# R3S601.net
KiCad netlist of a schematic drawn in Altium Designer
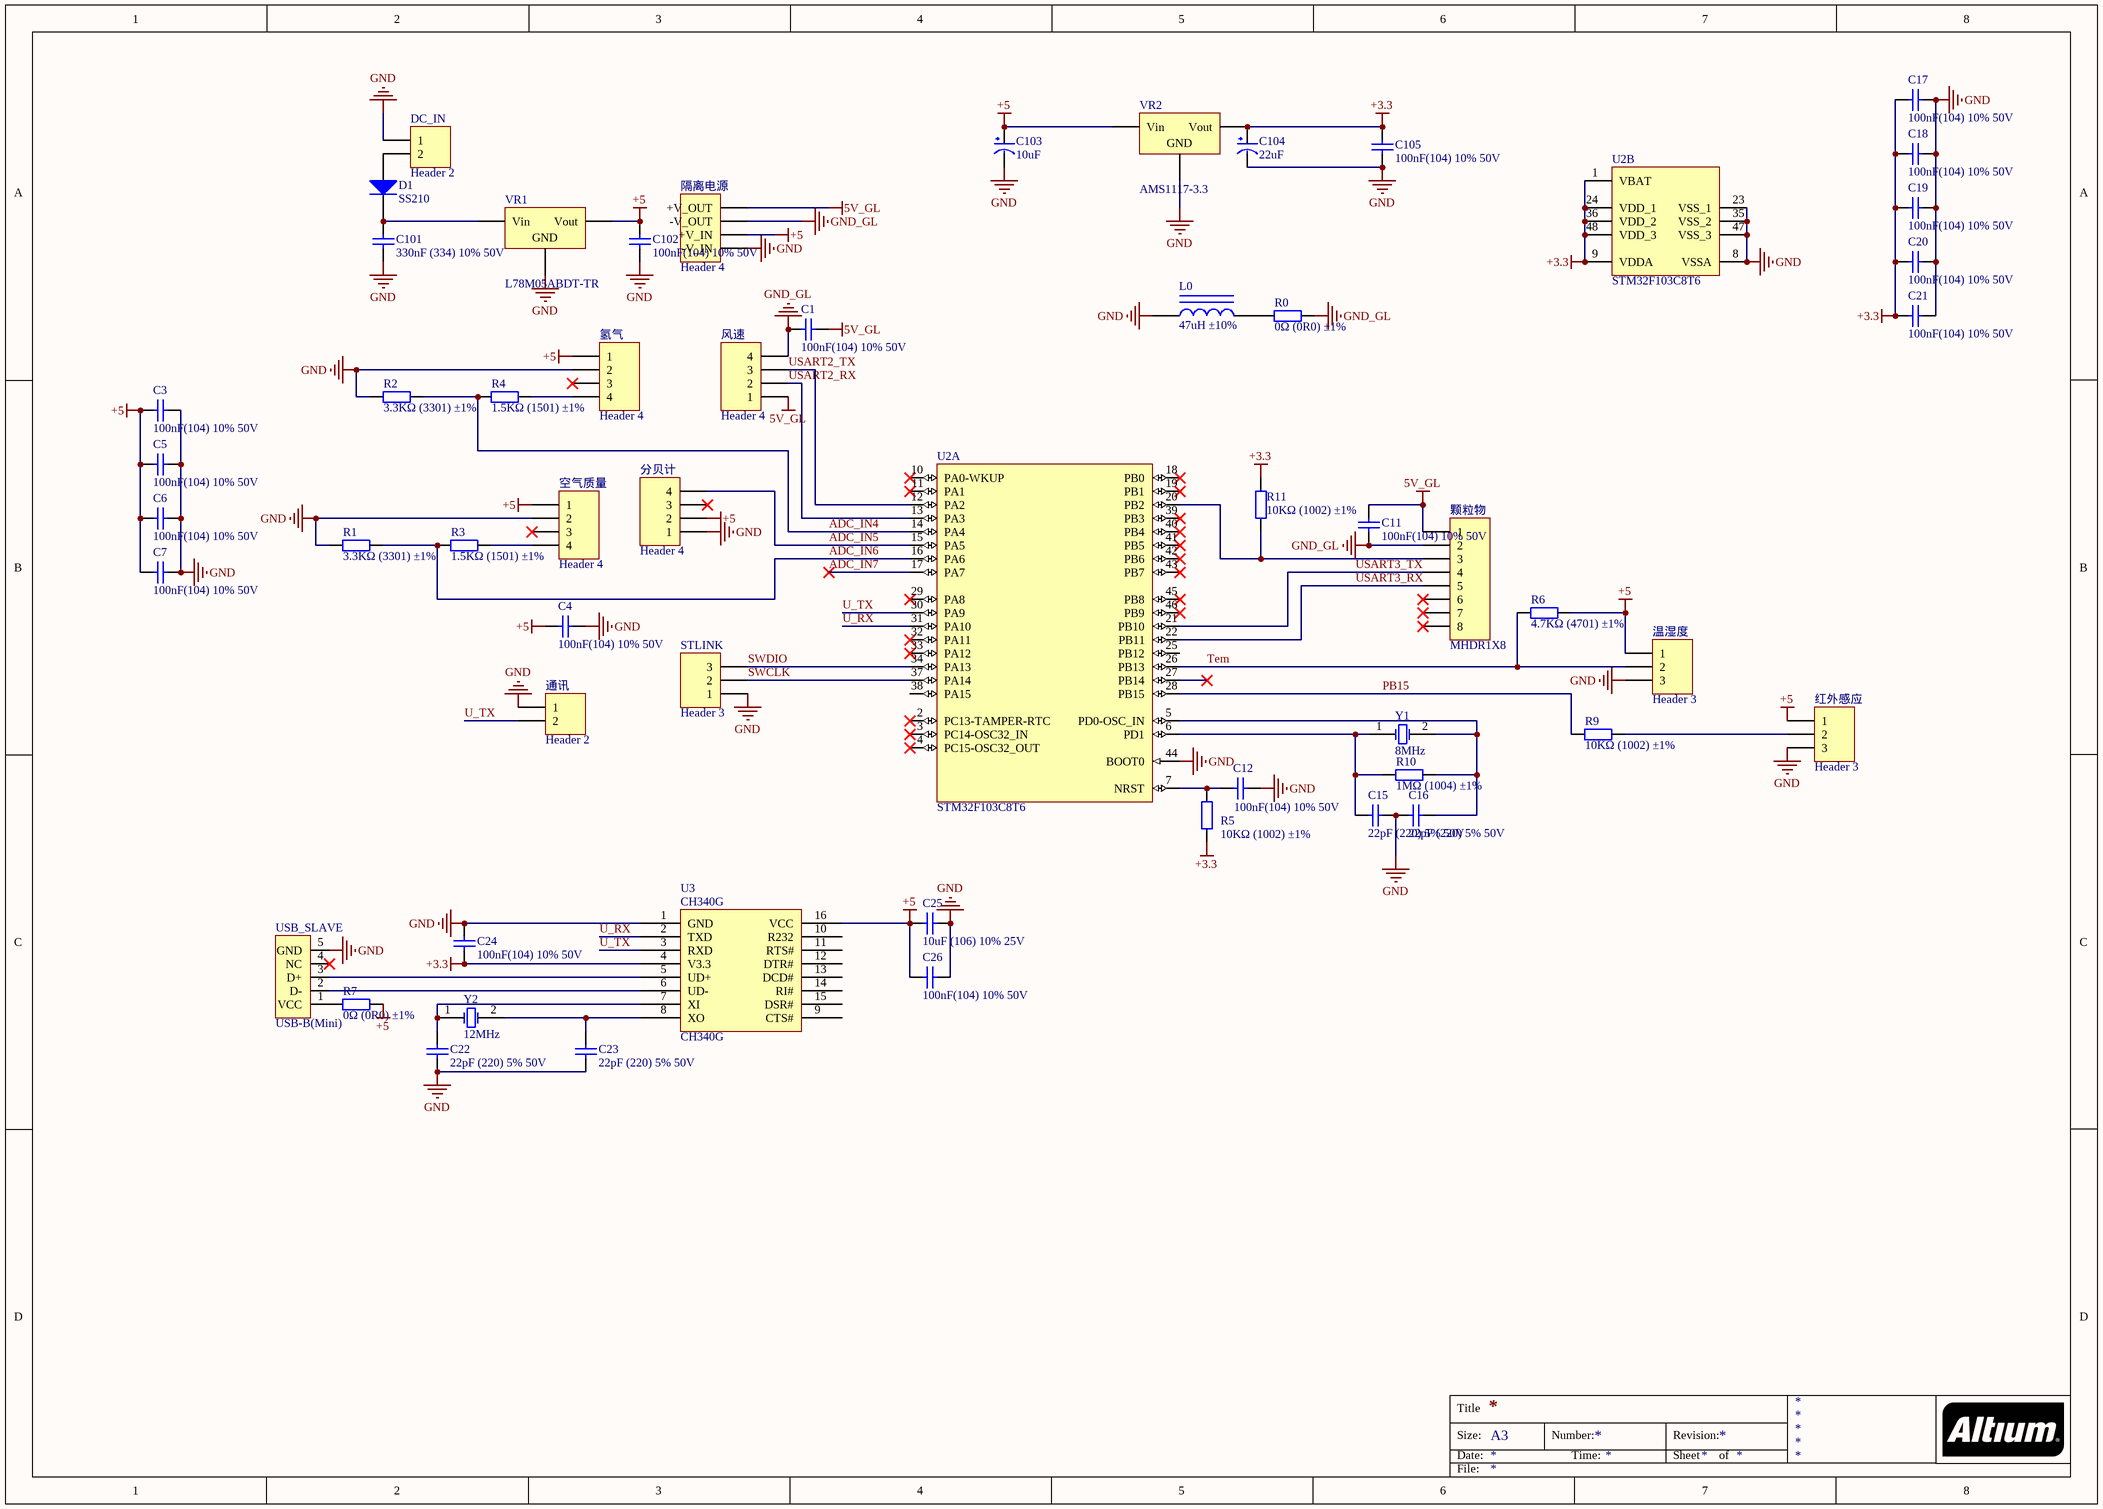
[diagram p0: R3S601.SchDoc]

(export (version "E")
  (design (tool "Eeschema 10.0.6"))
  (components
    (comp (ref "C1")
      (value "100nF(104) 10% 50V")
      (footprint "LC-0805_C")
      (description "贴片电容")
      (libsource (lib "Miscellaneous Devices LC") (part "0805 100nF(104) 10% 50V"))
    )
    (comp (ref "C3")
      (value "100nF(104) 10% 50V")
      (footprint "LC-0805_C")
      (description "贴片电容")
      (libsource (lib "Miscellaneous Devices LC") (part "0805 100nF(104) 10% 50V"))
    )
    (comp (ref "C4")
      (value "100nF(104) 10% 50V")
      (footprint "LC-0805_C")
      (description "贴片电容")
      (libsource (lib "Miscellaneous Devices LC") (part "0805 100nF(104) 10% 50V"))
    )
    (comp (ref "C5")
      (value "100nF(104) 10% 50V")
      (footprint "LC-0805_C")
      (description "贴片电容")
      (libsource (lib "Miscellaneous Devices LC") (part "0805 100nF(104) 10% 50V"))
    )
    (comp (ref "C6")
      (value "100nF(104) 10% 50V")
      (footprint "LC-0805_C")
      (description "贴片电容")
      (libsource (lib "Miscellaneous Devices LC") (part "0805 100nF(104) 10% 50V"))
    )
    (comp (ref "C7")
      (value "100nF(104) 10% 50V")
      (footprint "LC-0805_C")
      (description "贴片电容")
      (libsource (lib "Miscellaneous Devices LC") (part "0805 100nF(104) 10% 50V"))
    )
    (comp (ref "C11")
      (value "100nF(104) 10% 50V")
      (footprint "LC-0805_C")
      (description "贴片电容")
      (libsource (lib "Miscellaneous Devices LC") (part "0805 100nF(104) 10% 50V"))
    )
    (comp (ref "C12")
      (value "100nF(104) 10% 50V")
      (footprint "LC-0805_C")
      (description "贴片电容")
      (libsource (lib "Miscellaneous Devices LC") (part "0805 100nF(104) 10% 50V"))
    )
    (comp (ref "C15")
      (value "22pF (220) 5% 50V")
      (footprint "LC-0805_C")
      (description "贴片电容")
      (libsource (lib "Miscellaneous Devices LC") (part "0805 22pF (220) 5% 50V"))
    )
    (comp (ref "C16")
      (value "22pF (220) 5% 50V")
      (footprint "LC-0805_C")
      (description "贴片电容")
      (libsource (lib "Miscellaneous Devices LC") (part "0805 22pF (220) 5% 50V"))
    )
    (comp (ref "C17")
      (value "100nF(104) 10% 50V")
      (footprint "LC-0805_C")
      (description "贴片电容")
      (libsource (lib "Miscellaneous Devices LC") (part "0805 100nF(104) 10% 50V"))
    )
    (comp (ref "C18")
      (value "100nF(104) 10% 50V")
      (footprint "LC-0805_C")
      (description "贴片电容")
      (libsource (lib "Miscellaneous Devices LC") (part "0805 100nF(104) 10% 50V"))
    )
    (comp (ref "C19")
      (value "100nF(104) 10% 50V")
      (footprint "LC-0805_C")
      (description "贴片电容")
      (libsource (lib "Miscellaneous Devices LC") (part "0805 100nF(104) 10% 50V"))
    )
    (comp (ref "C20")
      (value "100nF(104) 10% 50V")
      (footprint "LC-0805_C")
      (description "贴片电容")
      (libsource (lib "Miscellaneous Devices LC") (part "0805 100nF(104) 10% 50V"))
    )
    (comp (ref "C21")
      (value "100nF(104) 10% 50V")
      (footprint "LC-0805_C")
      (description "贴片电容")
      (libsource (lib "Miscellaneous Devices LC") (part "0805 100nF(104) 10% 50V"))
    )
    (comp (ref "C22")
      (value "22pF (220) 5% 50V")
      (footprint "LC-0805_C")
      (description "贴片电容")
      (libsource (lib "Miscellaneous Devices LC") (part "0805 22pF (220) 5% 50V"))
    )
    (comp (ref "C23")
      (value "22pF (220) 5% 50V")
      (footprint "LC-0805_C")
      (description "贴片电容")
      (libsource (lib "Miscellaneous Devices LC") (part "0805 22pF (220) 5% 50V"))
    )
    (comp (ref "C24")
      (value "100nF(104) 10% 50V")
      (footprint "LC-0805_C")
      (description "贴片电容")
      (libsource (lib "Miscellaneous Devices LC") (part "0805 100nF(104) 10% 50V"))
    )
    (comp (ref "C25")
      (value "10uF (106) 10% 25V")
      (footprint "LC-0805_C")
      (description "贴片电容")
      (libsource (lib "Miscellaneous Devices LC") (part "0805 10uF (106) 10% 25V"))
    )
    (comp (ref "C26")
      (value "100nF(104) 10% 50V")
      (footprint "LC-0805_C")
      (description "贴片电容")
      (libsource (lib "Miscellaneous Devices LC") (part "0805 100nF(104) 10% 50V"))
    )
    (comp (ref "C101")
      (value "330nF (334) 10% 50V")
      (footprint "LC-0805_C")
      (description "贴片电容")
      (libsource (lib "Miscellaneous Devices LC") (part "0805 330nF (334) 10% 50V"))
    )
    (comp (ref "C102")
      (value "100nF(104) 10% 50V")
      (footprint "LC-0805_C")
      (description "贴片电容")
      (libsource (lib "Miscellaneous Devices LC") (part "0805 100nF(104) 10% 50V"))
    )
    (comp (ref "C103")
      (value "10uF")
      (footprint "CC6.56.5")
      (libsource (lib "Explorer STM32F407封装库") (part "CAP"))
    )
    (comp (ref "C104")
      (value "22uF")
      (footprint "CC6.56.5")
      (libsource (lib "Explorer STM32F407封装库") (part "CAP"))
    )
    (comp (ref "C105")
      (value "100nF(104) 10% 50V")
      (footprint "LC-0805_C")
      (description "贴片电容")
      (libsource (lib "Miscellaneous Devices LC") (part "0805 100nF(104) 10% 50V"))
    )
    (comp (ref "D1")
      (value "SS210")
      (footprint "LC-SMA(DO-214AC)_S1")
      (description "二极管")
      (libsource (lib "Miscellaneous Devices LC") (part "SMA(DO-214AC) SS210"))
    )
    (comp (ref "DC_IN")
      (value "Header 2")
      (footprint "HDR1X2")
      (description "Header, 2-Pin")
      (fields (field (name "PUBLISHER") "Altium Limited"))
      (libsource (lib "Miscellaneous Connectors") (part "Header 2"))
    )
    (comp (ref "L0")
      (value "47uH ±10%")
      (footprint "LC-0805_L")
      (description "贴片电感")
      (libsource (lib "Miscellaneous Devices LC") (part "0805 47uH 10%"))
    )
    (comp (ref "R0")
      (value "0Ω (0R0) ±1%")
      (footprint "LC-0603_R")
      (description "贴片电阻")
      (libsource (lib "Miscellaneous Devices LC") (part "0603 0Ω (0R0) 1%"))
    )
    (comp (ref "R1")
      (value "3.3KΩ (3301) ±1%")
      (footprint "LC-0805_R")
      (description "贴片电阻")
      (libsource (lib "Miscellaneous Devices LC") (part "0805 3.3KΩ (3301) 1%"))
    )
    (comp (ref "R2")
      (value "3.3KΩ (3301) ±1%")
      (footprint "LC-0805_R")
      (description "贴片电阻")
      (libsource (lib "Miscellaneous Devices LC") (part "0805 3.3KΩ (3301) 1%"))
    )
    (comp (ref "R3")
      (value "1.5KΩ (1501) ±1%")
      (footprint "LC-0805_R")
      (description "贴片电阻")
      (libsource (lib "Miscellaneous Devices LC") (part "0805 1.5KΩ (1501) 1%"))
    )
    (comp (ref "R4")
      (value "1.5KΩ (1501) ±1%")
      (footprint "LC-0805_R")
      (description "贴片电阻")
      (libsource (lib "Miscellaneous Devices LC") (part "0805 1.5KΩ (1501) 1%"))
    )
    (comp (ref "R5")
      (value "10KΩ (1002) ±1%")
      (footprint "LC-0805_R")
      (description "贴片电阻")
      (libsource (lib "") (part "0805 10KΩ (1002) 1%_1"))
    )
    (comp (ref "R6")
      (value "4.7KΩ (4701) ±1%")
      (footprint "LC-0805_R")
      (description "贴片电阻")
      (libsource (lib "Miscellaneous Devices LC") (part "0805 4.7KΩ (4701) 1%"))
    )
    (comp (ref "R7")
      (value "0Ω (0R0) ±1%")
      (footprint "LC-0805_R")
      (description "贴片电阻")
      (libsource (lib "Miscellaneous Devices LC") (part "0805 0Ω (0R0) 1%"))
    )
    (comp (ref "R9")
      (value "10KΩ (1002) ±1%")
      (footprint "LC-0805_R")
      (description "贴片电阻")
      (libsource (lib "Miscellaneous Devices LC") (part "0805 10KΩ (1002) 1%"))
    )
    (comp (ref "R10")
      (value "1MΩ (1004) ±1%")
      (footprint "LC-0805_R")
      (description "贴片电阻")
      (libsource (lib "Miscellaneous Devices LC") (part "0805 1MΩ (1004) 1%"))
    )
    (comp (ref "R11")
      (value "10KΩ (1002) ±1%")
      (footprint "LC-0805_R")
      (description "贴片电阻")
      (libsource (lib "") (part "0805 10KΩ (1002) 1%_1"))
    )
    (comp (ref "STLINK")
      (value "Header 3")
      (footprint "HDR1X3")
      (description "Header, 3-Pin")
      (fields (field (name "PUBLISHER") "Altium Limited"))
      (libsource (lib "Miscellaneous Connectors") (part "Header 3"))
    )
    (comp (ref "U2")
      (value "STM32F103C8T6")
      (footprint "LC-LQFP-48_7x7x05P")
      (description "ARM")
      (libsource (lib "Miscellaneous Devices LC") (part "STM32F103C8T6"))
    )
    (comp (ref "U3")
      (value "CH340G")
      (footprint "LC-SOIC-16_150mil")
      (description "USB")
      (libsource (lib "Miscellaneous Devices LC") (part "CH340G"))
    )
    (comp (ref "USB_SLAVE")
      (value "USB-B(Mini)")
      (footprint "USB/SM0.8-6H5")
      (libsource (lib "Explorer STM32F407封装库") (part "USB5"))
    )
    (comp (ref "VR1")
      (value "L78M05ABDT-TR")
      (footprint "LC-TO-252-2-180")
      (description "低压差线性稳压(LDO)")
      (libsource (lib "Miscellaneous Devices LC") (part "TO-252-2 L78M05ABDT-TR"))
    )
    (comp (ref "VR2")
      (value "AMS1117-3.3")
      (footprint "LC-SOT-223")
      (description "低压差线性稳压(LDO)")
      (libsource (lib "Miscellaneous Devices LC") (part "SOT-223 AMS1117-3.3"))
    )
    (comp (ref "Y1")
      (value "8MHz")
      (footprint "XTAL_US")
      (description "Crystal Oscillator")
      (fields (field (name "PUBLISHER") "Altium Limited"))
      (libsource (lib "Explorer STM32F407封装库") (part "XTAL"))
    )
    (comp (ref "Y2")
      (value "12MHz")
      (footprint "XTAL_US")
      (description "Crystal Oscillator")
      (fields (field (name "PUBLISHER") "Altium Limited"))
      (libsource (lib "Explorer STM32F407封装库") (part "XTAL"))
    )
    (comp (ref "分贝计")
      (value "Header 4")
      (footprint "HDR1X4")
      (description "Header, 4-Pin")
      (fields (field (name "PUBLISHER") "Altium Limited"))
      (libsource (lib "Miscellaneous Connectors") (part "Header 4"))
    )
    (comp (ref "氢气")
      (value "Header 4")
      (footprint "HDR1X4")
      (description "Header, 4-Pin")
      (fields (field (name "PUBLISHER") "Altium Limited"))
      (libsource (lib "") (part "Header 4_1"))
    )
    (comp (ref "温湿度")
      (value "Header 3")
      (footprint "HDR1X3")
      (description "Header, 3-Pin")
      (fields (field (name "PUBLISHER") "Altium Limited"))
      (libsource (lib "") (part "Header 3_1"))
    )
    (comp (ref "空气质量")
      (value "Header 4")
      (footprint "HDR1X4")
      (description "Header, 4-Pin")
      (fields (field (name "PUBLISHER") "Altium Limited"))
      (libsource (lib "") (part "Header 4_1"))
    )
    (comp (ref "红外感应")
      (value "Header 3")
      (footprint "HDR1X3")
      (description "Header, 3-Pin")
      (fields (field (name "PUBLISHER") "Altium Limited"))
      (libsource (lib "") (part "Header 3_1"))
    )
    (comp (ref "通讯")
      (value "Header 2")
      (footprint "HDR1X2")
      (description "Header, 2-Pin")
      (fields (field (name "PUBLISHER") "Altium Limited"))
      (libsource (lib "Miscellaneous Connectors") (part "Header 2"))
    )
    (comp (ref "隔离电源")
      (value "Header 4")
      (footprint "HDR1X4")
      (description "Header, 4-Pin")
      (fields (field (name "PUBLISHER") "Altium Limited"))
      (libsource (lib "Miscellaneous Connectors") (part "Header 4"))
    )
    (comp (ref "颗粒物")
      (value "MHDR1X8")
      (footprint "MHDR1X8")
      (description "Header, 8-Pin")
      (fields (field (name "PUBLISHER") "Altium Limited"))
      (libsource (lib "Miscellaneous Connectors") (part "MHDR1X8"))
    )
    (comp (ref "风速")
      (value "Header 4")
      (footprint "HDR1X4")
      (description "Header, 4-Pin")
      (fields (field (name "PUBLISHER") "Altium Limited"))
      (libsource (lib "Miscellaneous Connectors") (part "Header 4"))
    )
  )
  (nets
    (net (code "1") (name "+3.3") (class "Default")
      (node (ref "C104") (pin "1") (pinfunction "VCC_1") (pintype "passive"))
      (node (ref "C105") (pin "2") (pinfunction "2_2") (pintype "passive"))
      (node (ref "C17") (pin "2") (pinfunction "2_2") (pintype "passive"))
      (node (ref "C18") (pin "2") (pinfunction "2_2") (pintype "passive"))
      (node (ref "C19") (pin "2") (pinfunction "2_2") (pintype "passive"))
      (node (ref "C20") (pin "2") (pinfunction "2_2") (pintype "passive"))
      (node (ref "C21") (pin "2") (pinfunction "2_2") (pintype "passive"))
      (node (ref "C24") (pin "1") (pinfunction "1_1") (pintype "passive"))
      (node (ref "R11") (pin "2") (pinfunction "2_2") (pintype "passive"))
      (node (ref "R5") (pin "1") (pinfunction "1_1") (pintype "passive"))
      (node (ref "U2") (pin "1") (pinfunction "VBAT_1") (pintype "power_in"))
      (node (ref "U2") (pin "24") (pinfunction "VDD_1_24") (pintype "power_in"))
      (node (ref "U2") (pin "36") (pinfunction "VDD_2_36") (pintype "power_in"))
      (node (ref "U2") (pin "48") (pinfunction "VDD_3_48") (pintype "power_in"))
      (node (ref "U2") (pin "9") (pinfunction "VDDA_9") (pintype "power_in"))
      (node (ref "U3") (pin "4") (pinfunction "V3.3_4") (pintype "passive"))
      (node (ref "VR2") (pin "2") (pinfunction "Vout_2") (pintype "passive"))
    )
    (net (code "2") (name "+5") (class "Default")
      (node (ref "C102") (pin "2") (pinfunction "2_2") (pintype "passive"))
      (node (ref "C103") (pin "1") (pinfunction "VCC_1") (pintype "passive"))
      (node (ref "C25") (pin "1") (pinfunction "1_1") (pintype "passive"))
      (node (ref "C26") (pin "1") (pinfunction "1_1") (pintype "passive"))
      (node (ref "C3") (pin "1") (pinfunction "1_1") (pintype "passive"))
      (node (ref "C4") (pin "1") (pinfunction "1_1") (pintype "passive"))
      (node (ref "C5") (pin "1") (pinfunction "1_1") (pintype "passive"))
      (node (ref "C6") (pin "1") (pinfunction "1_1") (pintype "passive"))
      (node (ref "C7") (pin "1") (pinfunction "1_1") (pintype "passive"))
      (node (ref "R6") (pin "2") (pinfunction "2_2") (pintype "passive"))
      (node (ref "R7") (pin "2") (pinfunction "2_2") (pintype "passive"))
      (node (ref "U3") (pin "16") (pinfunction "VCC_16") (pintype "passive"))
      (node (ref "VR1") (pin "3") (pinfunction "Vout_3") (pintype "passive"))
      (node (ref "VR2") (pin "3") (pinfunction "Vin_3") (pintype "passive"))
      (node (ref "分贝计") (pin "2") (pinfunction "2_2") (pintype "passive"))
      (node (ref "氢气") (pin "1") (pinfunction "1_1") (pintype "passive"))
      (node (ref "温湿度") (pin "1") (pinfunction "1_1") (pintype "passive"))
      (node (ref "空气质量") (pin "1") (pinfunction "1_1") (pintype "passive"))
      (node (ref "红外感应") (pin "1") (pinfunction "1_1") (pintype "passive"))
      (node (ref "隔离电源") (pin "2") (pinfunction "2_2") (pintype "passive"))
    )
    (net (code "3") (name "/ADC_IN4") (class "Default")
      (node (ref "R2") (pin "2") (pinfunction "2_2") (pintype "passive"))
      (node (ref "R4") (pin "1") (pinfunction "1_1") (pintype "passive"))
      (node (ref "U2") (pin "14") (pinfunction "PA4_14") (pintype "bidirectional"))
    )
    (net (code "4") (name "/ADC_IN5") (class "Default")
      (node (ref "U2") (pin "15") (pinfunction "PA5_15") (pintype "bidirectional"))
      (node (ref "分贝计") (pin "4") (pinfunction "4_4") (pintype "passive"))
    )
    (net (code "5") (name "/ADC_IN6") (class "Default")
      (node (ref "R1") (pin "2") (pinfunction "2_2") (pintype "passive"))
      (node (ref "R3") (pin "1") (pinfunction "1_1") (pintype "passive"))
      (node (ref "U2") (pin "16") (pinfunction "PA6_16") (pintype "bidirectional"))
    )
    (net (code "6") (name "/ADC_IN7") (class "Default")
      (node (ref "U2") (pin "17") (pinfunction "PA7_17") (pintype "bidirectional+no_connect"))
    )
    (net (code "7") (name "/PB15") (class "Default")
      (node (ref "R9") (pin "1") (pinfunction "1_1") (pintype "passive"))
      (node (ref "U2") (pin "28") (pinfunction "PB15_28") (pintype "bidirectional"))
    )
    (net (code "8") (name "/SWCLK") (class "Default")
      (node (ref "STLINK") (pin "2") (pinfunction "2_2") (pintype "passive"))
      (node (ref "U2") (pin "37") (pinfunction "PA14_37") (pintype "bidirectional"))
    )
    (net (code "9") (name "/SWDIO") (class "Default")
      (node (ref "STLINK") (pin "3") (pinfunction "3_3") (pintype "passive"))
      (node (ref "U2") (pin "34") (pinfunction "PA13_34") (pintype "bidirectional"))
    )
    (net (code "10") (name "/Tem") (class "Default")
      (node (ref "R6") (pin "1") (pinfunction "1_1") (pintype "passive"))
      (node (ref "U2") (pin "26") (pinfunction "PB13_26") (pintype "bidirectional"))
      (node (ref "温湿度") (pin "2") (pinfunction "2_2") (pintype "passive"))
    )
    (net (code "11") (name "/USART2_RX") (class "Default")
      (node (ref "U2") (pin "13") (pinfunction "PA3_13") (pintype "bidirectional"))
      (node (ref "风速") (pin "2") (pinfunction "2_2") (pintype "passive"))
    )
    (net (code "12") (name "/USART2_TX") (class "Default")
      (node (ref "U2") (pin "12") (pinfunction "PA2_12") (pintype "bidirectional"))
      (node (ref "风速") (pin "3") (pinfunction "3_3") (pintype "passive"))
    )
    (net (code "13") (name "/USART3_RX") (class "Default")
      (node (ref "U2") (pin "22") (pinfunction "PB11_22") (pintype "bidirectional"))
      (node (ref "颗粒物") (pin "5") (pinfunction "5_5") (pintype "passive"))
    )
    (net (code "14") (name "/USART3_TX") (class "Default")
      (node (ref "U2") (pin "21") (pinfunction "PB10_21") (pintype "bidirectional"))
      (node (ref "颗粒物") (pin "4") (pinfunction "4_4") (pintype "passive"))
    )
    (net (code "15") (name "/U_RX") (class "Default")
      (node (ref "U2") (pin "31") (pinfunction "PA10_31") (pintype "bidirectional"))
      (node (ref "U3") (pin "2") (pinfunction "TXD_2") (pintype "passive"))
    )
    (net (code "16") (name "/U_TX") (class "Default")
      (node (ref "U2") (pin "30") (pinfunction "PA9_30") (pintype "bidirectional"))
      (node (ref "U3") (pin "3") (pinfunction "RXD_3") (pintype "passive"))
      (node (ref "通讯") (pin "2") (pinfunction "2_2") (pintype "passive"))
    )
    (net (code "17") (name "5V_GL") (class "Default")
      (node (ref "C1") (pin "2") (pinfunction "2_2") (pintype "passive"))
      (node (ref "C11") (pin "2") (pinfunction "2_2") (pintype "passive"))
      (node (ref "隔离电源") (pin "4") (pinfunction "4_4") (pintype "passive"))
      (node (ref "颗粒物") (pin "1") (pinfunction "1_1") (pintype "passive"))
      (node (ref "风速") (pin "1") (pinfunction "1_1") (pintype "passive"))
    )
    (net (code "18") (name "GND") (class "Default")
      (node (ref "C101") (pin "1") (pinfunction "1_1") (pintype "passive"))
      (node (ref "C102") (pin "1") (pinfunction "1_1") (pintype "passive"))
      (node (ref "C103") (pin "2") (pinfunction "GND_2") (pintype "passive"))
      (node (ref "C104") (pin "2") (pinfunction "GND_2") (pintype "passive"))
      (node (ref "C105") (pin "1") (pinfunction "1_1") (pintype "passive"))
      (node (ref "C12") (pin "1") (pinfunction "1_1") (pintype "passive"))
      (node (ref "C15") (pin "2") (pinfunction "2_2") (pintype "passive"))
      (node (ref "C16") (pin "1") (pinfunction "1_1") (pintype "passive"))
      (node (ref "C17") (pin "1") (pinfunction "1_1") (pintype "passive"))
      (node (ref "C18") (pin "1") (pinfunction "1_1") (pintype "passive"))
      (node (ref "C19") (pin "1") (pinfunction "1_1") (pintype "passive"))
      (node (ref "C20") (pin "1") (pinfunction "1_1") (pintype "passive"))
      (node (ref "C21") (pin "1") (pinfunction "1_1") (pintype "passive"))
      (node (ref "C22") (pin "1") (pinfunction "1_1") (pintype "passive"))
      (node (ref "C23") (pin "1") (pinfunction "1_1") (pintype "passive"))
      (node (ref "C24") (pin "2") (pinfunction "2_2") (pintype "passive"))
      (node (ref "C25") (pin "2") (pinfunction "2_2") (pintype "passive"))
      (node (ref "C26") (pin "2") (pinfunction "2_2") (pintype "passive"))
      (node (ref "C3") (pin "2") (pinfunction "2_2") (pintype "passive"))
      (node (ref "C4") (pin "2") (pinfunction "2_2") (pintype "passive"))
      (node (ref "C5") (pin "2") (pinfunction "2_2") (pintype "passive"))
      (node (ref "C6") (pin "2") (pinfunction "2_2") (pintype "passive"))
      (node (ref "C7") (pin "2") (pinfunction "2_2") (pintype "passive"))
      (node (ref "DC_IN") (pin "1") (pinfunction "1_1") (pintype "passive"))
      (node (ref "L0") (pin "1") (pinfunction "1_1") (pintype "passive"))
      (node (ref "R1") (pin "1") (pinfunction "1_1") (pintype "passive"))
      (node (ref "R2") (pin "1") (pinfunction "1_1") (pintype "passive"))
      (node (ref "STLINK") (pin "1") (pinfunction "1_1") (pintype "passive"))
      (node (ref "U2") (pin "23") (pinfunction "VSS_1_23") (pintype "power_in"))
      (node (ref "U2") (pin "35") (pinfunction "VSS_2_35") (pintype "power_in"))
      (node (ref "U2") (pin "44") (pinfunction "BOOT0_44") (pintype "input"))
      (node (ref "U2") (pin "47") (pinfunction "VSS_3_47") (pintype "power_in"))
      (node (ref "U2") (pin "8") (pinfunction "VSSA_8") (pintype "power_in"))
      (node (ref "U3") (pin "1") (pinfunction "GND_1") (pintype "passive"))
      (node (ref "USB_SLAVE") (pin "5") (pinfunction "GND_5") (pintype "passive"))
      (node (ref "VR1") (pin "2") (pinfunction "GND_2") (pintype "passive"))
      (node (ref "VR2") (pin "1") (pinfunction "GND_1") (pintype "passive"))
      (node (ref "分贝计") (pin "1") (pinfunction "1_1") (pintype "passive"))
      (node (ref "氢气") (pin "2") (pinfunction "2_2") (pintype "passive"))
      (node (ref "温湿度") (pin "3") (pinfunction "3_3") (pintype "passive"))
      (node (ref "空气质量") (pin "2") (pinfunction "2_2") (pintype "passive"))
      (node (ref "红外感应") (pin "3") (pinfunction "3_3") (pintype "passive"))
      (node (ref "通讯") (pin "1") (pinfunction "1_1") (pintype "passive"))
      (node (ref "隔离电源") (pin "1") (pinfunction "1_1") (pintype "passive"))
    )
    (net (code "19") (name "GND_GL") (class "Default")
      (node (ref "C1") (pin "1") (pinfunction "1_1") (pintype "passive"))
      (node (ref "C11") (pin "1") (pinfunction "1_1") (pintype "passive"))
      (node (ref "R0") (pin "2") (pinfunction "2_2") (pintype "passive"))
      (node (ref "隔离电源") (pin "3") (pinfunction "3_3") (pintype "passive"))
      (node (ref "颗粒物") (pin "2") (pinfunction "2_2") (pintype "passive"))
      (node (ref "风速") (pin "4") (pinfunction "4_4") (pintype "passive"))
    )
    (net (code "20") (name "Net-(D1-A)") (class "Default")
      (node (ref "D1") (pin "1") (pinfunction "A_1") (pintype "passive"))
      (node (ref "DC_IN") (pin "2") (pinfunction "2_2") (pintype "passive"))
    )
    (net (code "21") (name "Net-(D1-K)") (class "Default")
      (node (ref "C101") (pin "2") (pinfunction "2_2") (pintype "passive"))
      (node (ref "D1") (pin "2") (pinfunction "K_2") (pintype "passive"))
      (node (ref "VR1") (pin "1") (pinfunction "Vin_1") (pintype "passive"))
    )
    (net (code "22") (name "Net-(L0-Pad2)") (class "Default")
      (node (ref "L0") (pin "2") (pinfunction "2_2") (pintype "passive"))
      (node (ref "R0") (pin "1") (pinfunction "1_1") (pintype "passive"))
    )
    (net (code "23") (name "Net-(R3-Pad2)") (class "Default")
      (node (ref "R3") (pin "2") (pinfunction "2_2") (pintype "passive"))
      (node (ref "空气质量") (pin "4") (pinfunction "4_4") (pintype "passive"))
    )
    (net (code "24") (name "Net-(R4-Pad2)") (class "Default")
      (node (ref "R4") (pin "2") (pinfunction "2_2") (pintype "passive"))
      (node (ref "氢气") (pin "4") (pinfunction "4_4") (pintype "passive"))
    )
    (net (code "25") (name "Net-(R9-Pad2)") (class "Default")
      (node (ref "R9") (pin "2") (pinfunction "2_2") (pintype "passive"))
      (node (ref "红外感应") (pin "2") (pinfunction "2_2") (pintype "passive"))
    )
    (net (code "26") (name "Net-(U2A-NRST)") (class "Default")
      (node (ref "C12") (pin "2") (pinfunction "2_2") (pintype "passive"))
      (node (ref "R5") (pin "2") (pinfunction "2_2") (pintype "passive"))
      (node (ref "U2") (pin "7") (pinfunction "NRST_7") (pintype "bidirectional"))
    )
    (net (code "27") (name "Net-(U2A-PB2)") (class "Default")
      (node (ref "R11") (pin "1") (pinfunction "1_1") (pintype "passive"))
      (node (ref "U2") (pin "20") (pinfunction "PB2_20") (pintype "bidirectional"))
      (node (ref "颗粒物") (pin "3") (pinfunction "3_3") (pintype "passive"))
    )
    (net (code "28") (name "Net-(U2A-PD0-OSC_IN)") (class "Default")
      (node (ref "C16") (pin "2") (pinfunction "2_2") (pintype "passive"))
      (node (ref "R10") (pin "2") (pinfunction "2_2") (pintype "passive"))
      (node (ref "U2") (pin "5") (pinfunction "PD0-OSC_IN_5") (pintype "bidirectional"))
      (node (ref "Y1") (pin "2") (pinfunction "OSC2_2") (pintype "passive"))
    )
    (net (code "29") (name "Net-(U2A-PD1)") (class "Default")
      (node (ref "C15") (pin "1") (pinfunction "1_1") (pintype "passive"))
      (node (ref "R10") (pin "1") (pinfunction "1_1") (pintype "passive"))
      (node (ref "U2") (pin "6") (pinfunction "PD1_6") (pintype "bidirectional"))
      (node (ref "Y1") (pin "1") (pinfunction "OSC1_1") (pintype "passive"))
    )
    (net (code "30") (name "Net-(U3-UD+)") (class "Default")
      (node (ref "U3") (pin "5") (pinfunction "UD+_5") (pintype "passive"))
      (node (ref "USB_SLAVE") (pin "3") (pinfunction "D+_3") (pintype "passive"))
    )
    (net (code "31") (name "Net-(U3-UD-)") (class "Default")
      (node (ref "U3") (pin "6") (pinfunction "UD-_6") (pintype "passive"))
      (node (ref "USB_SLAVE") (pin "2") (pinfunction "D-_2") (pintype "passive"))
    )
    (net (code "32") (name "Net-(U3-XI)") (class "Default")
      (node (ref "C22") (pin "2") (pinfunction "2_2") (pintype "passive"))
      (node (ref "U3") (pin "7") (pinfunction "XI_7") (pintype "passive"))
      (node (ref "Y2") (pin "1") (pinfunction "OSC1_1") (pintype "passive"))
    )
    (net (code "33") (name "Net-(U3-XO)") (class "Default")
      (node (ref "C23") (pin "2") (pinfunction "2_2") (pintype "passive"))
      (node (ref "U3") (pin "8") (pinfunction "XO_8") (pintype "passive"))
      (node (ref "Y2") (pin "2") (pinfunction "OSC2_2") (pintype "passive"))
    )
    (net (code "34") (name "Net-(USB_SLAVE-VCC)") (class "Default")
      (node (ref "R7") (pin "1") (pinfunction "1_1") (pintype "passive"))
      (node (ref "USB_SLAVE") (pin "1") (pinfunction "VCC_1") (pintype "passive"))
    )
    (net (code "35") (name "unconnected-(U2A-PA0-WKUP-Pad10)") (class "Default")
      (node (ref "U2") (pin "10") (pinfunction "PA0-WKUP_10") (pintype "bidirectional+no_connect"))
    )
    (net (code "36") (name "unconnected-(U2A-PA1-Pad11)") (class "Default")
      (node (ref "U2") (pin "11") (pinfunction "PA1_11") (pintype "bidirectional+no_connect"))
    )
    (net (code "37") (name "unconnected-(U2A-PA8-Pad29)") (class "Default")
      (node (ref "U2") (pin "29") (pinfunction "PA8_29") (pintype "bidirectional+no_connect"))
    )
    (net (code "38") (name "unconnected-(U2A-PA11-Pad32)") (class "Default")
      (node (ref "U2") (pin "32") (pinfunction "PA11_32") (pintype "bidirectional+no_connect"))
    )
    (net (code "39") (name "unconnected-(U2A-PA12-Pad33)") (class "Default")
      (node (ref "U2") (pin "33") (pinfunction "PA12_33") (pintype "bidirectional+no_connect"))
    )
    (net (code "40") (name "unconnected-(U2A-PA15-Pad38)") (class "Default")
      (node (ref "U2") (pin "38") (pinfunction "PA15_38") (pintype "bidirectional"))
    )
    (net (code "41") (name "unconnected-(U2A-PB0-Pad18)") (class "Default")
      (node (ref "U2") (pin "18") (pinfunction "PB0_18") (pintype "bidirectional+no_connect"))
    )
    (net (code "42") (name "unconnected-(U2A-PB1-Pad19)") (class "Default")
      (node (ref "U2") (pin "19") (pinfunction "PB1_19") (pintype "bidirectional+no_connect"))
    )
    (net (code "43") (name "unconnected-(U2A-PB3-Pad39)") (class "Default")
      (node (ref "U2") (pin "39") (pinfunction "PB3_39") (pintype "bidirectional+no_connect"))
    )
    (net (code "44") (name "unconnected-(U2A-PB4-Pad40)") (class "Default")
      (node (ref "U2") (pin "40") (pinfunction "PB4_40") (pintype "bidirectional+no_connect"))
    )
    (net (code "45") (name "unconnected-(U2A-PB5-Pad41)") (class "Default")
      (node (ref "U2") (pin "41") (pinfunction "PB5_41") (pintype "bidirectional+no_connect"))
    )
    (net (code "46") (name "unconnected-(U2A-PB6-Pad42)") (class "Default")
      (node (ref "U2") (pin "42") (pinfunction "PB6_42") (pintype "bidirectional+no_connect"))
    )
    (net (code "47") (name "unconnected-(U2A-PB7-Pad43)") (class "Default")
      (node (ref "U2") (pin "43") (pinfunction "PB7_43") (pintype "bidirectional+no_connect"))
    )
    (net (code "48") (name "unconnected-(U2A-PB8-Pad45)") (class "Default")
      (node (ref "U2") (pin "45") (pinfunction "PB8_45") (pintype "bidirectional+no_connect"))
    )
    (net (code "49") (name "unconnected-(U2A-PB9-Pad46)") (class "Default")
      (node (ref "U2") (pin "46") (pinfunction "PB9_46") (pintype "bidirectional+no_connect"))
    )
    (net (code "50") (name "unconnected-(U2A-PB12-Pad25)") (class "Default")
      (node (ref "U2") (pin "25") (pinfunction "PB12_25") (pintype "bidirectional"))
    )
    (net (code "51") (name "unconnected-(U2A-PB14-Pad27)") (class "Default")
      (node (ref "U2") (pin "27") (pinfunction "PB14_27") (pintype "bidirectional+no_connect"))
    )
    (net (code "52") (name "unconnected-(U2A-PC13-TAMPER-RTC-Pad2)") (class "Default")
      (node (ref "U2") (pin "2") (pinfunction "PC13-TAMPER-RTC_2") (pintype "bidirectional+no_connect"))
    )
    (net (code "53") (name "unconnected-(U2A-PC14-OSC32_IN-Pad3)") (class "Default")
      (node (ref "U2") (pin "3") (pinfunction "PC14-OSC32_IN_3") (pintype "bidirectional+no_connect"))
    )
    (net (code "54") (name "unconnected-(U2A-PC15-OSC32_OUT-Pad4)") (class "Default")
      (node (ref "U2") (pin "4") (pinfunction "PC15-OSC32_OUT_4") (pintype "bidirectional+no_connect"))
    )
    (net (code "55") (name "unconnected-(U3-CTS#-Pad9)") (class "Default")
      (node (ref "U3") (pin "9") (pinfunction "CTS#_9") (pintype "passive"))
    )
    (net (code "56") (name "unconnected-(U3-DCD#-Pad13)") (class "Default")
      (node (ref "U3") (pin "13") (pinfunction "DCD#_13") (pintype "passive"))
    )
    (net (code "57") (name "unconnected-(U3-DSR#-Pad15)") (class "Default")
      (node (ref "U3") (pin "15") (pinfunction "DSR#_15") (pintype "passive"))
    )
    (net (code "58") (name "unconnected-(U3-DTR#-Pad12)") (class "Default")
      (node (ref "U3") (pin "12") (pinfunction "DTR#_12") (pintype "passive"))
    )
    (net (code "59") (name "unconnected-(U3-R232-Pad10)") (class "Default")
      (node (ref "U3") (pin "10") (pinfunction "R232_10") (pintype "passive"))
    )
    (net (code "60") (name "unconnected-(U3-RI#-Pad14)") (class "Default")
      (node (ref "U3") (pin "14") (pinfunction "RI#_14") (pintype "passive"))
    )
    (net (code "61") (name "unconnected-(U3-RTS#-Pad11)") (class "Default")
      (node (ref "U3") (pin "11") (pinfunction "RTS#_11") (pintype "passive"))
    )
    (net (code "62") (name "unconnected-(USB_SLAVE-NC-Pad4)") (class "Default")
      (node (ref "USB_SLAVE") (pin "4") (pinfunction "NC_4") (pintype "passive+no_connect"))
    )
    (net (code "63") (name "unconnected-(分贝计-Pad3)") (class "Default")
      (node (ref "分贝计") (pin "3") (pinfunction "3_3") (pintype "passive+no_connect"))
    )
    (net (code "64") (name "unconnected-(氢气-Pad3)") (class "Default")
      (node (ref "氢气") (pin "3") (pinfunction "3_3") (pintype "passive+no_connect"))
    )
    (net (code "65") (name "unconnected-(空气质量-Pad3)") (class "Default")
      (node (ref "空气质量") (pin "3") (pinfunction "3_3") (pintype "passive+no_connect"))
    )
    (net (code "66") (name "unconnected-(颗粒物-Pad6)") (class "Default")
      (node (ref "颗粒物") (pin "6") (pinfunction "6_6") (pintype "passive+no_connect"))
    )
    (net (code "67") (name "unconnected-(颗粒物-Pad7)") (class "Default")
      (node (ref "颗粒物") (pin "7") (pinfunction "7_7") (pintype "passive+no_connect"))
    )
    (net (code "68") (name "unconnected-(颗粒物-Pad8)") (class "Default")
      (node (ref "颗粒物") (pin "8") (pinfunction "8_8") (pintype "passive+no_connect"))
    )
  )
)
